# LCD.net
KiCad netlist of a schematic drawn in Altium Designer
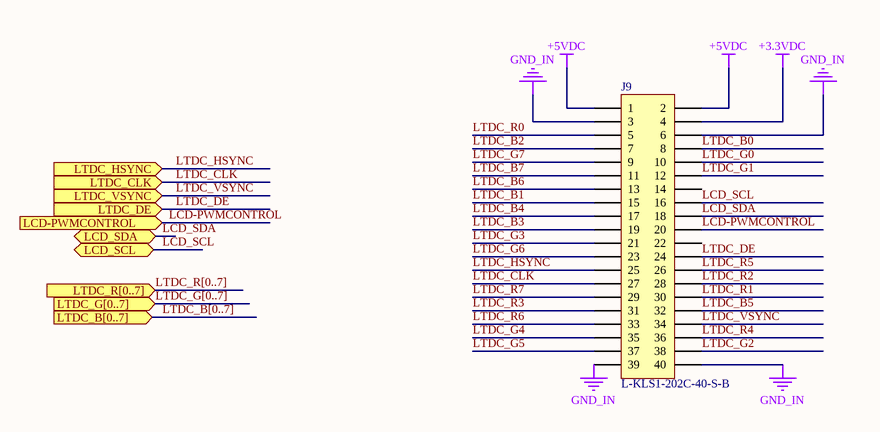
[diagram p0: LCD.SchDoc]

(export (version "E")
  (design (tool "Eeschema 10.0.6"))
  (components
    (comp (ref "J9")
      (value "L-KLS1-202C-40-S-B")
      (footprint "L-KLS1-202C-40-T-B")
      (description "BOX HEADER 40PIN(2x20) 1.27MM THT V/T MALE BLACK")
      (libsource (lib "IM_v1.0") (part "2X20"))
    )
  )
  (nets
    (net (code "1") (name "+3.3VDC") (class "Default")
      (node (ref "J9") (pin "4") (pinfunction "4_4") (pintype "passive"))
    )
    (net (code "2") (name "+5VDC") (class "Default")
      (node (ref "J9") (pin "1") (pinfunction "1_1") (pintype "passive"))
      (node (ref "J9") (pin "2") (pinfunction "2_2") (pintype "passive"))
    )
    (net (code "3") (name "/LCD-PWMCONTROL") (class "Default")
      (node (ref "J9") (pin "20") (pinfunction "20_20") (pintype "passive"))
    )
    (net (code "4") (name "/LCD_SCL") (class "Default")
      (node (ref "J9") (pin "16") (pinfunction "16_16") (pintype "passive"))
    )
    (net (code "5") (name "/LCD_SDA") (class "Default")
      (node (ref "J9") (pin "18") (pinfunction "18_18") (pintype "passive"))
    )
    (net (code "6") (name "/LTDC_B0") (class "Default")
      (node (ref "J9") (pin "8") (pinfunction "8_8") (pintype "passive"))
    )
    (net (code "7") (name "/LTDC_B1") (class "Default")
      (node (ref "J9") (pin "15") (pinfunction "15_15") (pintype "passive"))
    )
    (net (code "8") (name "/LTDC_B2") (class "Default")
      (node (ref "J9") (pin "7") (pinfunction "7_7") (pintype "passive"))
    )
    (net (code "9") (name "/LTDC_B3") (class "Default")
      (node (ref "J9") (pin "19") (pinfunction "19_19") (pintype "passive"))
    )
    (net (code "10") (name "/LTDC_B4") (class "Default")
      (node (ref "J9") (pin "17") (pinfunction "17_17") (pintype "passive"))
    )
    (net (code "11") (name "/LTDC_B5") (class "Default")
      (node (ref "J9") (pin "32") (pinfunction "32_32") (pintype "passive"))
    )
    (net (code "12") (name "/LTDC_B6") (class "Default")
      (node (ref "J9") (pin "13") (pinfunction "13_13") (pintype "passive"))
    )
    (net (code "13") (name "/LTDC_B7") (class "Default")
      (node (ref "J9") (pin "11") (pinfunction "11_11") (pintype "passive"))
    )
    (net (code "15") (name "/LTDC_CLK") (class "Default")
      (node (ref "J9") (pin "27") (pinfunction "27_27") (pintype "passive"))
    )
    (net (code "16") (name "/LTDC_DE") (class "Default")
      (node (ref "J9") (pin "24") (pinfunction "24_24") (pintype "passive"))
    )
    (net (code "17") (name "/LTDC_G0") (class "Default")
      (node (ref "J9") (pin "10") (pinfunction "10_10") (pintype "passive"))
    )
    (net (code "18") (name "/LTDC_G1") (class "Default")
      (node (ref "J9") (pin "12") (pinfunction "12_12") (pintype "passive"))
    )
    (net (code "19") (name "/LTDC_G2") (class "Default")
      (node (ref "J9") (pin "38") (pinfunction "38_38") (pintype "passive"))
    )
    (net (code "20") (name "/LTDC_G3") (class "Default")
      (node (ref "J9") (pin "21") (pinfunction "21_21") (pintype "passive"))
    )
    (net (code "21") (name "/LTDC_G4") (class "Default")
      (node (ref "J9") (pin "35") (pinfunction "35_35") (pintype "passive"))
    )
    (net (code "22") (name "/LTDC_G5") (class "Default")
      (node (ref "J9") (pin "37") (pinfunction "37_37") (pintype "passive"))
    )
    (net (code "23") (name "/LTDC_G6") (class "Default")
      (node (ref "J9") (pin "23") (pinfunction "23_23") (pintype "passive"))
    )
    (net (code "24") (name "/LTDC_G7") (class "Default")
      (node (ref "J9") (pin "9") (pinfunction "9_9") (pintype "passive"))
    )
    (net (code "26") (name "/LTDC_HSYNC") (class "Default")
      (node (ref "J9") (pin "25") (pinfunction "25_25") (pintype "passive"))
    )
    (net (code "27") (name "/LTDC_R0") (class "Default")
      (node (ref "J9") (pin "5") (pinfunction "5_5") (pintype "passive"))
    )
    (net (code "28") (name "/LTDC_R1") (class "Default")
      (node (ref "J9") (pin "30") (pinfunction "30_30") (pintype "passive"))
    )
    (net (code "29") (name "/LTDC_R2") (class "Default")
      (node (ref "J9") (pin "28") (pinfunction "28_28") (pintype "passive"))
    )
    (net (code "30") (name "/LTDC_R3") (class "Default")
      (node (ref "J9") (pin "31") (pinfunction "31_31") (pintype "passive"))
    )
    (net (code "31") (name "/LTDC_R4") (class "Default")
      (node (ref "J9") (pin "36") (pinfunction "36_36") (pintype "passive"))
    )
    (net (code "32") (name "/LTDC_R5") (class "Default")
      (node (ref "J9") (pin "26") (pinfunction "26_26") (pintype "passive"))
    )
    (net (code "33") (name "/LTDC_R6") (class "Default")
      (node (ref "J9") (pin "33") (pinfunction "33_33") (pintype "passive"))
    )
    (net (code "34") (name "/LTDC_R7") (class "Default")
      (node (ref "J9") (pin "29") (pinfunction "29_29") (pintype "passive"))
    )
    (net (code "36") (name "/LTDC_VSYNC") (class "Default")
      (node (ref "J9") (pin "34") (pinfunction "34_34") (pintype "passive"))
    )
    (net (code "37") (name "GND_IN") (class "Default")
      (node (ref "J9") (pin "3") (pinfunction "3_3") (pintype "passive"))
      (node (ref "J9") (pin "39") (pinfunction "39_39") (pintype "passive"))
      (node (ref "J9") (pin "40") (pinfunction "40_40") (pintype "passive"))
      (node (ref "J9") (pin "6") (pinfunction "6_6") (pintype "passive"))
    )
    (net (code "38") (name "unconnected-(J9-Pad14)") (class "Default")
      (node (ref "J9") (pin "14") (pinfunction "14_14") (pintype "passive"))
    )
    (net (code "39") (name "unconnected-(J9-Pad22)") (class "Default")
      (node (ref "J9") (pin "22") (pinfunction "22_22") (pintype "passive"))
    )
  )
)
